# DAC.net
KiCad netlist of a schematic drawn in Altium Designer
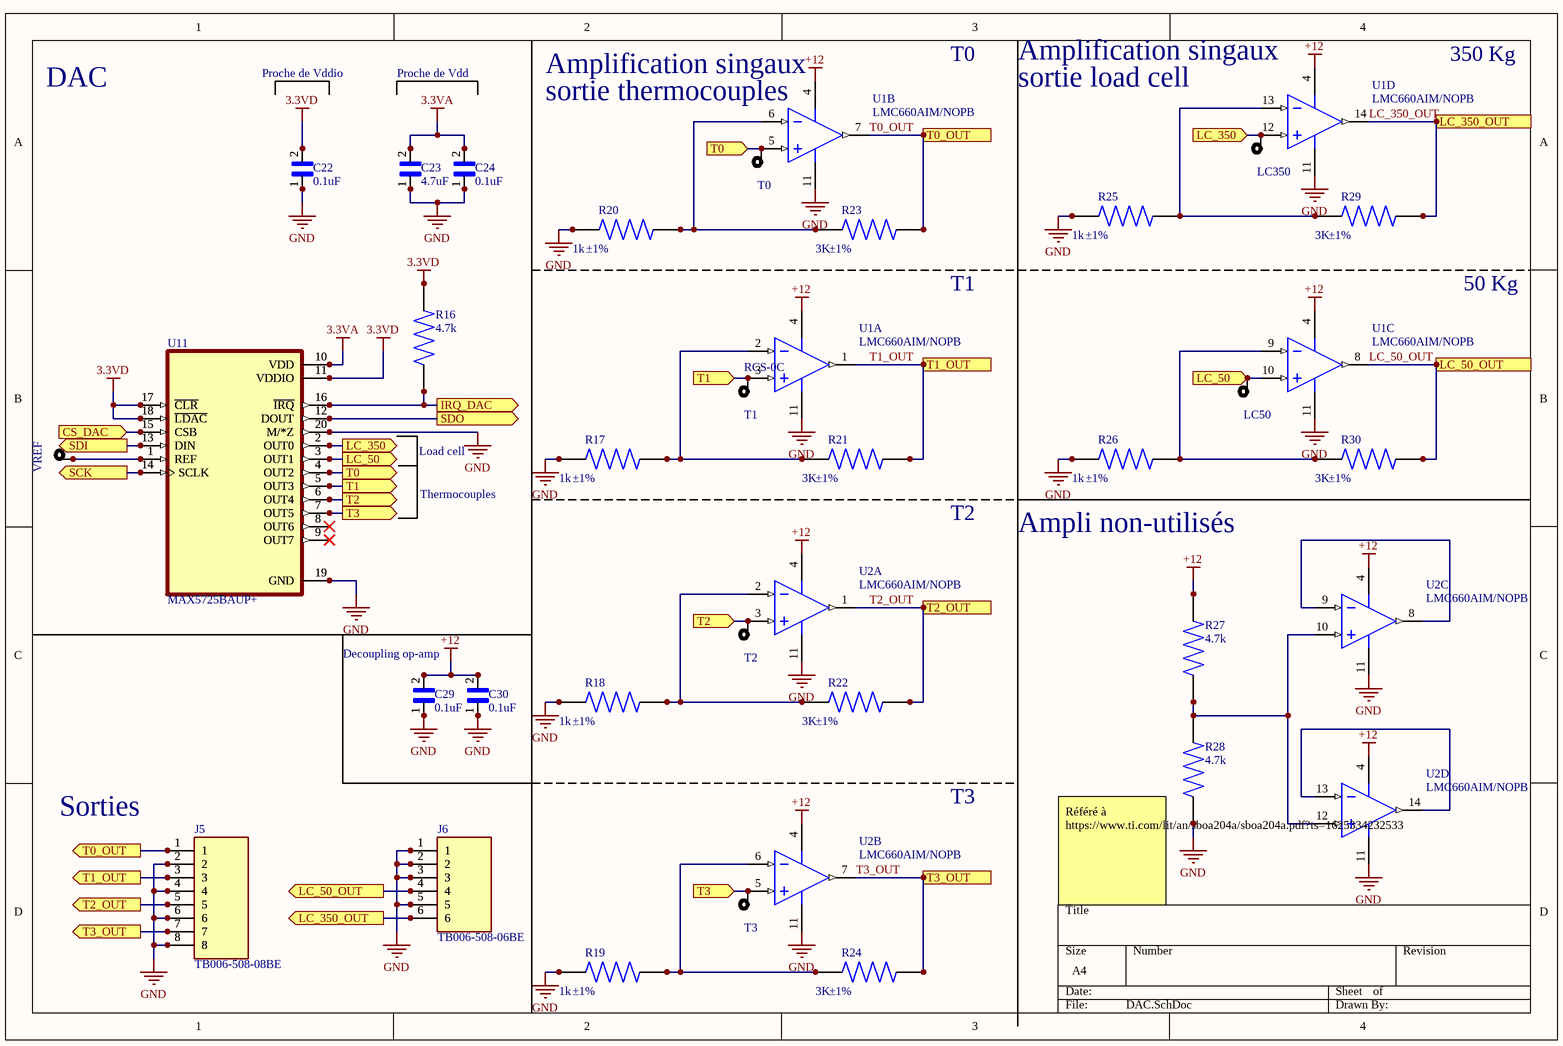
[diagram p0: DAC.SchDoc]

(export (version "E")
  (design (tool "Eeschema 10.0.6"))
  (components
    (comp (ref "C22")
      (value "0.1uF")
      (footprint "C3216C0G1H104J160AA")
      (fields (field (name "Comment") "C3216C0G1H104J160AA"))
      (libsource (lib "C3216C0G1H104J160AA") (part "C3216C0G1H104J160AA"))
    )
    (comp (ref "C23")
      (value "4.7uF")
      (footprint "EMK212BB7475MD-T")
      (description "CAP CER 4.7UF 16V X7R 0805")
      (fields (field (name "Comment") "EMK212BB7475MD-T"))
      (libsource (lib "EMK212BB7475MD-T") (part "EMK212BB7475MD-T"))
    )
    (comp (ref "C24")
      (value "0.1uF")
      (footprint "C3216C0G1H104J160AA")
      (fields (field (name "Comment") "C3216C0G1H104J160AA"))
      (libsource (lib "C3216C0G1H104J160AA") (part "C3216C0G1H104J160AA"))
    )
    (comp (ref "C29")
      (value "0.1uF")
      (footprint "C3216C0G1H104J160AA")
      (fields (field (name "Comment") "C3216C0G1H104J160AA"))
      (libsource (lib "C3216C0G1H104J160AA") (part "C3216C0G1H104J160AA"))
    )
    (comp (ref "C30")
      (value "0.1uF")
      (footprint "C3216C0G1H104J160AA")
      (fields (field (name "Comment") "C3216C0G1H104J160AA"))
      (libsource (lib "C3216C0G1H104J160AA") (part "C3216C0G1H104J160AA"))
    )
    (comp (ref "J5")
      (value "TB006-508-08BE")
      (footprint "TB006-508-08BE")
      (libsource (lib "TB006-508-08BE") (part "TB006-508-08BE"))
    )
    (comp (ref "J6")
      (value "TB006-508-06BE")
      (footprint "TB006-508-06BE")
      (description "TERMINAL BLOCK, SCREW TYPE, 5.08")
      (libsource (lib "TB006-508-06BE") (part "TB006-508-06BE"))
    )
    (comp (ref "LC50")
      (value "RCS-0C")
      (footprint "RCS-0C")
      (description "PC TEST POINT NATURAL")
      (libsource (lib "RCS-0C") (part "RCS-0C"))
    )
    (comp (ref "LC350")
      (value "RCS-0C")
      (footprint "RCS-0C")
      (description "PC TEST POINT NATURAL")
      (libsource (lib "RCS-0C") (part "RCS-0C"))
    )
    (comp (ref "R16")
      (value "4.7k")
      (footprint "CRGH0805F4K7")
      (description "CRGH0805 1% 4K7 0.33W")
      (fields (field (name "TOLERANCE") "±1%") (field (name "Comment") "CRGH0805F4K7"))
      (libsource (lib "CRGH0805F4K7") (part "CRGH0805F4K7"))
    )
    (comp (ref "R17")
      (value "1k")
      (footprint "CR0805-FX-1001ELF")
      (description "1 kOhms ±1% 0.125W, 1/8W Chip Resistor 0805")
      (fields (field (name "TOLERANCE") "±1%") (field (name "Comment") "CR0805-FX-1001ELF"))
      (libsource (lib "CR0805-FX-1001ELF") (part "CR0805-FX-1001ELF"))
    )
    (comp (ref "R18")
      (value "1k")
      (footprint "CR0805-FX-1001ELF")
      (description "1 kOhms ±1% 0.125W, 1/8W Chip Resistor 0805")
      (fields (field (name "TOLERANCE") "±1%") (field (name "Comment") "CR0805-FX-1001ELF"))
      (libsource (lib "CR0805-FX-1001ELF") (part "CR0805-FX-1001ELF"))
    )
    (comp (ref "R19")
      (value "1k")
      (footprint "CR0805-FX-1001ELF")
      (description "1 kOhms ±1% 0.125W, 1/8W Chip Resistor 0805")
      (fields (field (name "TOLERANCE") "±1%") (field (name "Comment") "CR0805-FX-1001ELF"))
      (libsource (lib "CR0805-FX-1001ELF") (part "CR0805-FX-1001ELF"))
    )
    (comp (ref "R20")
      (value "1k")
      (footprint "CR0805-FX-1001ELF")
      (description "1 kOhms ±1% 0.125W, 1/8W Chip Resistor 0805")
      (fields (field (name "TOLERANCE") "±1%") (field (name "Comment") "CR0805-FX-1001ELF"))
      (libsource (lib "CR0805-FX-1001ELF") (part "CR0805-FX-1001ELF"))
    )
    (comp (ref "R21")
      (value "3K")
      (footprint "CRG0805F3K0")
      (description "RES SMD 3K OHM 1% 1/8W 0805")
      (fields (field (name "TOLERANCE") "±1%") (field (name "Comment") "CRG0805F3K0"))
      (libsource (lib "CRG0805F3K0") (part "CRG0805F3K0"))
    )
    (comp (ref "R22")
      (value "3K")
      (footprint "CRG0805F3K0")
      (description "RES SMD 3K OHM 1% 1/8W 0805")
      (fields (field (name "TOLERANCE") "±1%") (field (name "Comment") "CRG0805F3K0"))
      (libsource (lib "CRG0805F3K0") (part "CRG0805F3K0"))
    )
    (comp (ref "R23")
      (value "3K")
      (footprint "CRG0805F3K0")
      (description "RES SMD 3K OHM 1% 1/8W 0805")
      (fields (field (name "TOLERANCE") "±1%") (field (name "Comment") "CRG0805F3K0"))
      (libsource (lib "CRG0805F3K0") (part "CRG0805F3K0"))
    )
    (comp (ref "R24")
      (value "3K")
      (footprint "CRG0805F3K0")
      (description "RES SMD 3K OHM 1% 1/8W 0805")
      (fields (field (name "TOLERANCE") "±1%") (field (name "Comment") "CRG0805F3K0"))
      (libsource (lib "CRG0805F3K0") (part "CRG0805F3K0"))
    )
    (comp (ref "R25")
      (value "1k")
      (footprint "CR0805-FX-1001ELF")
      (description "1 kOhms ±1% 0.125W, 1/8W Chip Resistor 0805")
      (fields (field (name "TOLERANCE") "±1%") (field (name "Comment") "CR0805-FX-1001ELF"))
      (libsource (lib "CR0805-FX-1001ELF") (part "CR0805-FX-1001ELF"))
    )
    (comp (ref "R26")
      (value "1k")
      (footprint "CR0805-FX-1001ELF")
      (description "1 kOhms ±1% 0.125W, 1/8W Chip Resistor 0805")
      (fields (field (name "TOLERANCE") "±1%") (field (name "Comment") "CR0805-FX-1001ELF"))
      (libsource (lib "CR0805-FX-1001ELF") (part "CR0805-FX-1001ELF"))
    )
    (comp (ref "R27")
      (value "4.7k")
      (footprint "CRGH0805F4K7")
      (description "CRGH0805 1% 4K7 0.33W")
      (fields (field (name "TOLERANCE") "±1%") (field (name "Comment") "CRGH0805F4K7"))
      (libsource (lib "CRGH0805F4K7") (part "CRGH0805F4K7"))
    )
    (comp (ref "R28")
      (value "4.7k")
      (footprint "CRGH0805F4K7")
      (description "CRGH0805 1% 4K7 0.33W")
      (fields (field (name "TOLERANCE") "±1%") (field (name "Comment") "CRGH0805F4K7"))
      (libsource (lib "CRGH0805F4K7") (part "CRGH0805F4K7"))
    )
    (comp (ref "R29")
      (value "3K")
      (footprint "CRG0805F3K0")
      (description "RES SMD 3K OHM 1% 1/8W 0805")
      (fields (field (name "TOLERANCE") "±1%") (field (name "Comment") "CRG0805F3K0"))
      (libsource (lib "CRG0805F3K0") (part "CRG0805F3K0"))
    )
    (comp (ref "R30")
      (value "3K")
      (footprint "CRG0805F3K0")
      (description "RES SMD 3K OHM 1% 1/8W 0805")
      (fields (field (name "TOLERANCE") "±1%") (field (name "Comment") "CRG0805F3K0"))
      (libsource (lib "CRG0805F3K0") (part "CRG0805F3K0"))
    )
    (comp (ref "T0")
      (value "RCS-0C")
      (footprint "RCS-0C")
      (description "PC TEST POINT NATURAL")
      (libsource (lib "RCS-0C") (part "RCS-0C"))
    )
    (comp (ref "T1")
      (value "RCS-0C")
      (footprint "RCS-0C")
      (description "PC TEST POINT NATURAL")
      (libsource (lib "RCS-0C") (part "RCS-0C"))
    )
    (comp (ref "T2")
      (value "RCS-0C")
      (footprint "RCS-0C")
      (description "PC TEST POINT NATURAL")
      (libsource (lib "RCS-0C") (part "RCS-0C"))
    )
    (comp (ref "T3")
      (value "RCS-0C")
      (footprint "RCS-0C")
      (description "PC TEST POINT NATURAL")
      (libsource (lib "RCS-0C") (part "RCS-0C"))
    )
    (comp (ref "U1")
      (value "LMC660AIM/NOPB")
      (footprint "D0014A_N")
      (description "CMOS Quad Operational Amplifier, 14-pin Narrow SOIC, Pb-Free")
      (fields (field (name "MANUFACTURER") "Texas Instruments"))
      (libsource (lib "Altium Content Vault") (part "AMP-OPA-LF147-14"))
    )
    (comp (ref "U2")
      (value "LMC660AIM/NOPB")
      (footprint "D0014A_N")
      (description "CMOS Quad Operational Amplifier, 14-pin Narrow SOIC, Pb-Free")
      (fields (field (name "MANUFACTURER") "Texas Instruments"))
      (libsource (lib "Altium Content Vault") (part "AMP-OPA-LF147-14"))
    )
    (comp (ref "U11")
      (value "MAX5725BAUP+")
      (footprint "MAX5725BAUP+")
      (description "IC DAC 12BIT V-OUT 20TSSOP")
      (libsource (lib "MAX5725") (part "MAX5725BAUP"))
    )
    (comp (ref "VREF")
      (value "RCS-0C")
      (footprint "RCS-0C")
      (description "PC TEST POINT NATURAL")
      (libsource (lib "RCS-0C") (part "RCS-0C"))
    )
  )
  (nets
    (net (code "1") (name "+12") (class "Default")
      (node (ref "C29") (pin "2") (pinfunction "2_2") (pintype "passive"))
      (node (ref "C30") (pin "2") (pinfunction "2_2") (pintype "passive"))
      (node (ref "R27") (pin "2") (pinfunction "2_2") (pintype "passive"))
      (node (ref "U1") (pin "4") (pinfunction "V+_4") (pintype "power_in"))
      (node (ref "U2") (pin "4") (pinfunction "V+_4") (pintype "power_in"))
    )
    (net (code "2") (name "/CS_DAC") (class "Default")
      (node (ref "U11") (pin "15") (pinfunction "CSB_15") (pintype "input"))
    )
    (net (code "3") (name "/IRQ_DAC") (class "Default")
      (node (ref "R16") (pin "1") (pinfunction "1_1") (pintype "passive"))
      (node (ref "U11") (pin "16") (pinfunction "~{IRQ}_16") (pintype "output"))
    )
    (net (code "4") (name "/LC_50") (class "Default")
      (node (ref "LC50") (pin "1") (pinfunction "1_1") (pintype "passive"))
      (node (ref "U1") (pin "10") (pinfunction "IN3+_10") (pintype "input"))
      (node (ref "U11") (pin "3") (pinfunction "OUT1_3") (pintype "output"))
    )
    (net (code "5") (name "/LC_50_OUT") (class "Default")
      (node (ref "J6") (pin "4") (pinfunction "4_4") (pintype "passive"))
      (node (ref "R30") (pin "2") (pinfunction "2_2") (pintype "passive"))
      (node (ref "U1") (pin "8") (pinfunction "OUT3_8") (pintype "output"))
    )
    (net (code "6") (name "/LC_350") (class "Default")
      (node (ref "LC350") (pin "1") (pinfunction "1_1") (pintype "passive"))
      (node (ref "U1") (pin "12") (pinfunction "IN4+_12") (pintype "input"))
      (node (ref "U11") (pin "2") (pinfunction "OUT0_2") (pintype "output"))
    )
    (net (code "7") (name "/LC_350_OUT") (class "Default")
      (node (ref "J6") (pin "6") (pinfunction "6_6") (pintype "passive"))
      (node (ref "R29") (pin "2") (pinfunction "2_2") (pintype "passive"))
      (node (ref "U1") (pin "14") (pinfunction "OUT4_14") (pintype "output"))
    )
    (net (code "8") (name "/SCK") (class "Default")
      (node (ref "U11") (pin "14") (pinfunction "SCLK_14") (pintype "input"))
    )
    (net (code "9") (name "/SDI") (class "Default")
      (node (ref "U11") (pin "13") (pinfunction "DIN_13") (pintype "input"))
    )
    (net (code "10") (name "/SDO") (class "Default")
      (node (ref "U11") (pin "12") (pinfunction "DOUT_12") (pintype "output"))
    )
    (net (code "11") (name "/T0") (class "Default")
      (node (ref "T0") (pin "1") (pinfunction "1_1") (pintype "passive"))
      (node (ref "U1") (pin "5") (pinfunction "IN2+_5") (pintype "input"))
      (node (ref "U11") (pin "4") (pinfunction "OUT2_4") (pintype "output"))
    )
    (net (code "12") (name "/T0_OUT") (class "Default")
      (node (ref "J5") (pin "1") (pinfunction "1_1") (pintype "passive"))
      (node (ref "R23") (pin "2") (pinfunction "2_2") (pintype "passive"))
      (node (ref "U1") (pin "7") (pinfunction "OUT2_7") (pintype "output"))
    )
    (net (code "13") (name "/T1") (class "Default")
      (node (ref "T1") (pin "1") (pinfunction "1_1") (pintype "passive"))
      (node (ref "U1") (pin "3") (pinfunction "IN1+_3") (pintype "input"))
      (node (ref "U11") (pin "5") (pinfunction "OUT3_5") (pintype "output"))
    )
    (net (code "14") (name "/T1_OUT") (class "Default")
      (node (ref "J5") (pin "3") (pinfunction "3_3") (pintype "passive"))
      (node (ref "R21") (pin "2") (pinfunction "2_2") (pintype "passive"))
      (node (ref "U1") (pin "1") (pinfunction "OUT1_1") (pintype "output"))
    )
    (net (code "15") (name "/T2") (class "Default")
      (node (ref "T2") (pin "1") (pinfunction "1_1") (pintype "passive"))
      (node (ref "U11") (pin "6") (pinfunction "OUT4_6") (pintype "output"))
      (node (ref "U2") (pin "3") (pinfunction "IN1+_3") (pintype "input"))
    )
    (net (code "16") (name "/T2_OUT") (class "Default")
      (node (ref "J5") (pin "5") (pinfunction "5_5") (pintype "passive"))
      (node (ref "R22") (pin "2") (pinfunction "2_2") (pintype "passive"))
      (node (ref "U2") (pin "1") (pinfunction "OUT1_1") (pintype "output"))
    )
    (net (code "17") (name "/T3") (class "Default")
      (node (ref "T3") (pin "1") (pinfunction "1_1") (pintype "passive"))
      (node (ref "U11") (pin "7") (pinfunction "OUT5_7") (pintype "output"))
      (node (ref "U2") (pin "5") (pinfunction "IN2+_5") (pintype "input"))
    )
    (net (code "18") (name "/T3_OUT") (class "Default")
      (node (ref "J5") (pin "7") (pinfunction "7_7") (pintype "passive"))
      (node (ref "R24") (pin "2") (pinfunction "2_2") (pintype "passive"))
      (node (ref "U2") (pin "7") (pinfunction "OUT2_7") (pintype "output"))
    )
    (net (code "19") (name "3.3VA") (class "Default")
      (node (ref "C23") (pin "2") (pinfunction "2_2") (pintype "passive"))
      (node (ref "C24") (pin "2") (pinfunction "2_2") (pintype "passive"))
      (node (ref "U11") (pin "10") (pinfunction "VDD_10") (pintype "power_in"))
    )
    (net (code "20") (name "3.3VD") (class "Default")
      (node (ref "C22") (pin "2") (pinfunction "2_2") (pintype "passive"))
      (node (ref "R16") (pin "2") (pinfunction "2_2") (pintype "passive"))
      (node (ref "U11") (pin "11") (pinfunction "VDDIO_11") (pintype "power_in"))
      (node (ref "U11") (pin "17") (pinfunction "~{CLR}_17") (pintype "input"))
      (node (ref "U11") (pin "18") (pinfunction "~{LDAC}_18") (pintype "input"))
    )
    (net (code "21") (name "GND") (class "Default")
      (node (ref "C22") (pin "1") (pinfunction "1_1") (pintype "passive"))
      (node (ref "C23") (pin "1") (pinfunction "1_1") (pintype "passive"))
      (node (ref "C24") (pin "1") (pinfunction "1_1") (pintype "passive"))
      (node (ref "C29") (pin "1") (pinfunction "1_1") (pintype "passive"))
      (node (ref "C30") (pin "1") (pinfunction "1_1") (pintype "passive"))
      (node (ref "J5") (pin "2") (pinfunction "2_2") (pintype "passive"))
      (node (ref "J5") (pin "4") (pinfunction "4_4") (pintype "passive"))
      (node (ref "J5") (pin "6") (pinfunction "6_6") (pintype "passive"))
      (node (ref "J5") (pin "8") (pinfunction "8_8") (pintype "passive"))
      (node (ref "J6") (pin "1") (pinfunction "1_1") (pintype "passive"))
      (node (ref "J6") (pin "2") (pinfunction "2_2") (pintype "passive"))
      (node (ref "J6") (pin "3") (pinfunction "3_3") (pintype "passive"))
      (node (ref "J6") (pin "5") (pinfunction "5_5") (pintype "passive"))
      (node (ref "R17") (pin "1") (pinfunction "1_1") (pintype "passive"))
      (node (ref "R18") (pin "1") (pinfunction "1_1") (pintype "passive"))
      (node (ref "R19") (pin "1") (pinfunction "1_1") (pintype "passive"))
      (node (ref "R20") (pin "1") (pinfunction "1_1") (pintype "passive"))
      (node (ref "R25") (pin "1") (pinfunction "1_1") (pintype "passive"))
      (node (ref "R26") (pin "1") (pinfunction "1_1") (pintype "passive"))
      (node (ref "R28") (pin "1") (pinfunction "1_1") (pintype "passive"))
      (node (ref "U1") (pin "11") (pinfunction "V-_11") (pintype "power_in"))
      (node (ref "U11") (pin "19") (pinfunction "GND_19") (pintype "power_in"))
      (node (ref "U11") (pin "20") (pinfunction "M/*Z_20") (pintype "output"))
      (node (ref "U2") (pin "11") (pinfunction "V-_11") (pintype "power_in"))
    )
    (net (code "22") (name "Net-(U1A-IN1-)") (class "Default")
      (node (ref "R17") (pin "2") (pinfunction "2_2") (pintype "passive"))
      (node (ref "R21") (pin "1") (pinfunction "1_1") (pintype "passive"))
      (node (ref "U1") (pin "2") (pinfunction "IN1-_2") (pintype "input"))
    )
    (net (code "23") (name "Net-(U1B-IN2-)") (class "Default")
      (node (ref "R20") (pin "2") (pinfunction "2_2") (pintype "passive"))
      (node (ref "R23") (pin "1") (pinfunction "1_1") (pintype "passive"))
      (node (ref "U1") (pin "6") (pinfunction "IN2-_6") (pintype "input"))
    )
    (net (code "24") (name "Net-(U1C-IN3-)") (class "Default")
      (node (ref "R26") (pin "2") (pinfunction "2_2") (pintype "passive"))
      (node (ref "R30") (pin "1") (pinfunction "1_1") (pintype "passive"))
      (node (ref "U1") (pin "9") (pinfunction "IN3-_9") (pintype "input"))
    )
    (net (code "25") (name "Net-(U1D-IN4-)") (class "Default")
      (node (ref "R25") (pin "2") (pinfunction "2_2") (pintype "passive"))
      (node (ref "R29") (pin "1") (pinfunction "1_1") (pintype "passive"))
      (node (ref "U1") (pin "13") (pinfunction "IN4-_13") (pintype "input"))
    )
    (net (code "26") (name "Net-(U2A-IN1-)") (class "Default")
      (node (ref "R18") (pin "2") (pinfunction "2_2") (pintype "passive"))
      (node (ref "R22") (pin "1") (pinfunction "1_1") (pintype "passive"))
      (node (ref "U2") (pin "2") (pinfunction "IN1-_2") (pintype "input"))
    )
    (net (code "27") (name "Net-(U2B-IN2-)") (class "Default")
      (node (ref "R19") (pin "2") (pinfunction "2_2") (pintype "passive"))
      (node (ref "R24") (pin "1") (pinfunction "1_1") (pintype "passive"))
      (node (ref "U2") (pin "6") (pinfunction "IN2-_6") (pintype "input"))
    )
    (net (code "28") (name "Net-(U2C-IN3+)") (class "Default")
      (node (ref "R27") (pin "1") (pinfunction "1_1") (pintype "passive"))
      (node (ref "R28") (pin "2") (pinfunction "2_2") (pintype "passive"))
      (node (ref "U2") (pin "10") (pinfunction "IN3+_10") (pintype "input"))
      (node (ref "U2") (pin "12") (pinfunction "IN4+_12") (pintype "input"))
    )
    (net (code "29") (name "Net-(U2C-IN3-)") (class "Default")
      (node (ref "U2") (pin "8") (pinfunction "OUT3_8") (pintype "output"))
      (node (ref "U2") (pin "9") (pinfunction "IN3-_9") (pintype "input"))
    )
    (net (code "30") (name "Net-(U2D-IN4-)") (class "Default")
      (node (ref "U2") (pin "13") (pinfunction "IN4-_13") (pintype "input"))
      (node (ref "U2") (pin "14") (pinfunction "OUT4_14") (pintype "output"))
    )
    (net (code "31") (name "Net-(U11-REF)") (class "Default")
      (node (ref "U11") (pin "1") (pinfunction "REF_1") (pintype "input"))
      (node (ref "VREF") (pin "1") (pinfunction "1_1") (pintype "passive"))
    )
    (net (code "32") (name "unconnected-(U11-OUT6-Pad8)") (class "Default")
      (node (ref "U11") (pin "8") (pinfunction "OUT6_8") (pintype "output+no_connect"))
    )
    (net (code "33") (name "unconnected-(U11-OUT7-Pad9)") (class "Default")
      (node (ref "U11") (pin "9") (pinfunction "OUT7_9") (pintype "output+no_connect"))
    )
  )
)
